# Top.net
KiCad netlist of a schematic drawn in Altium Designer
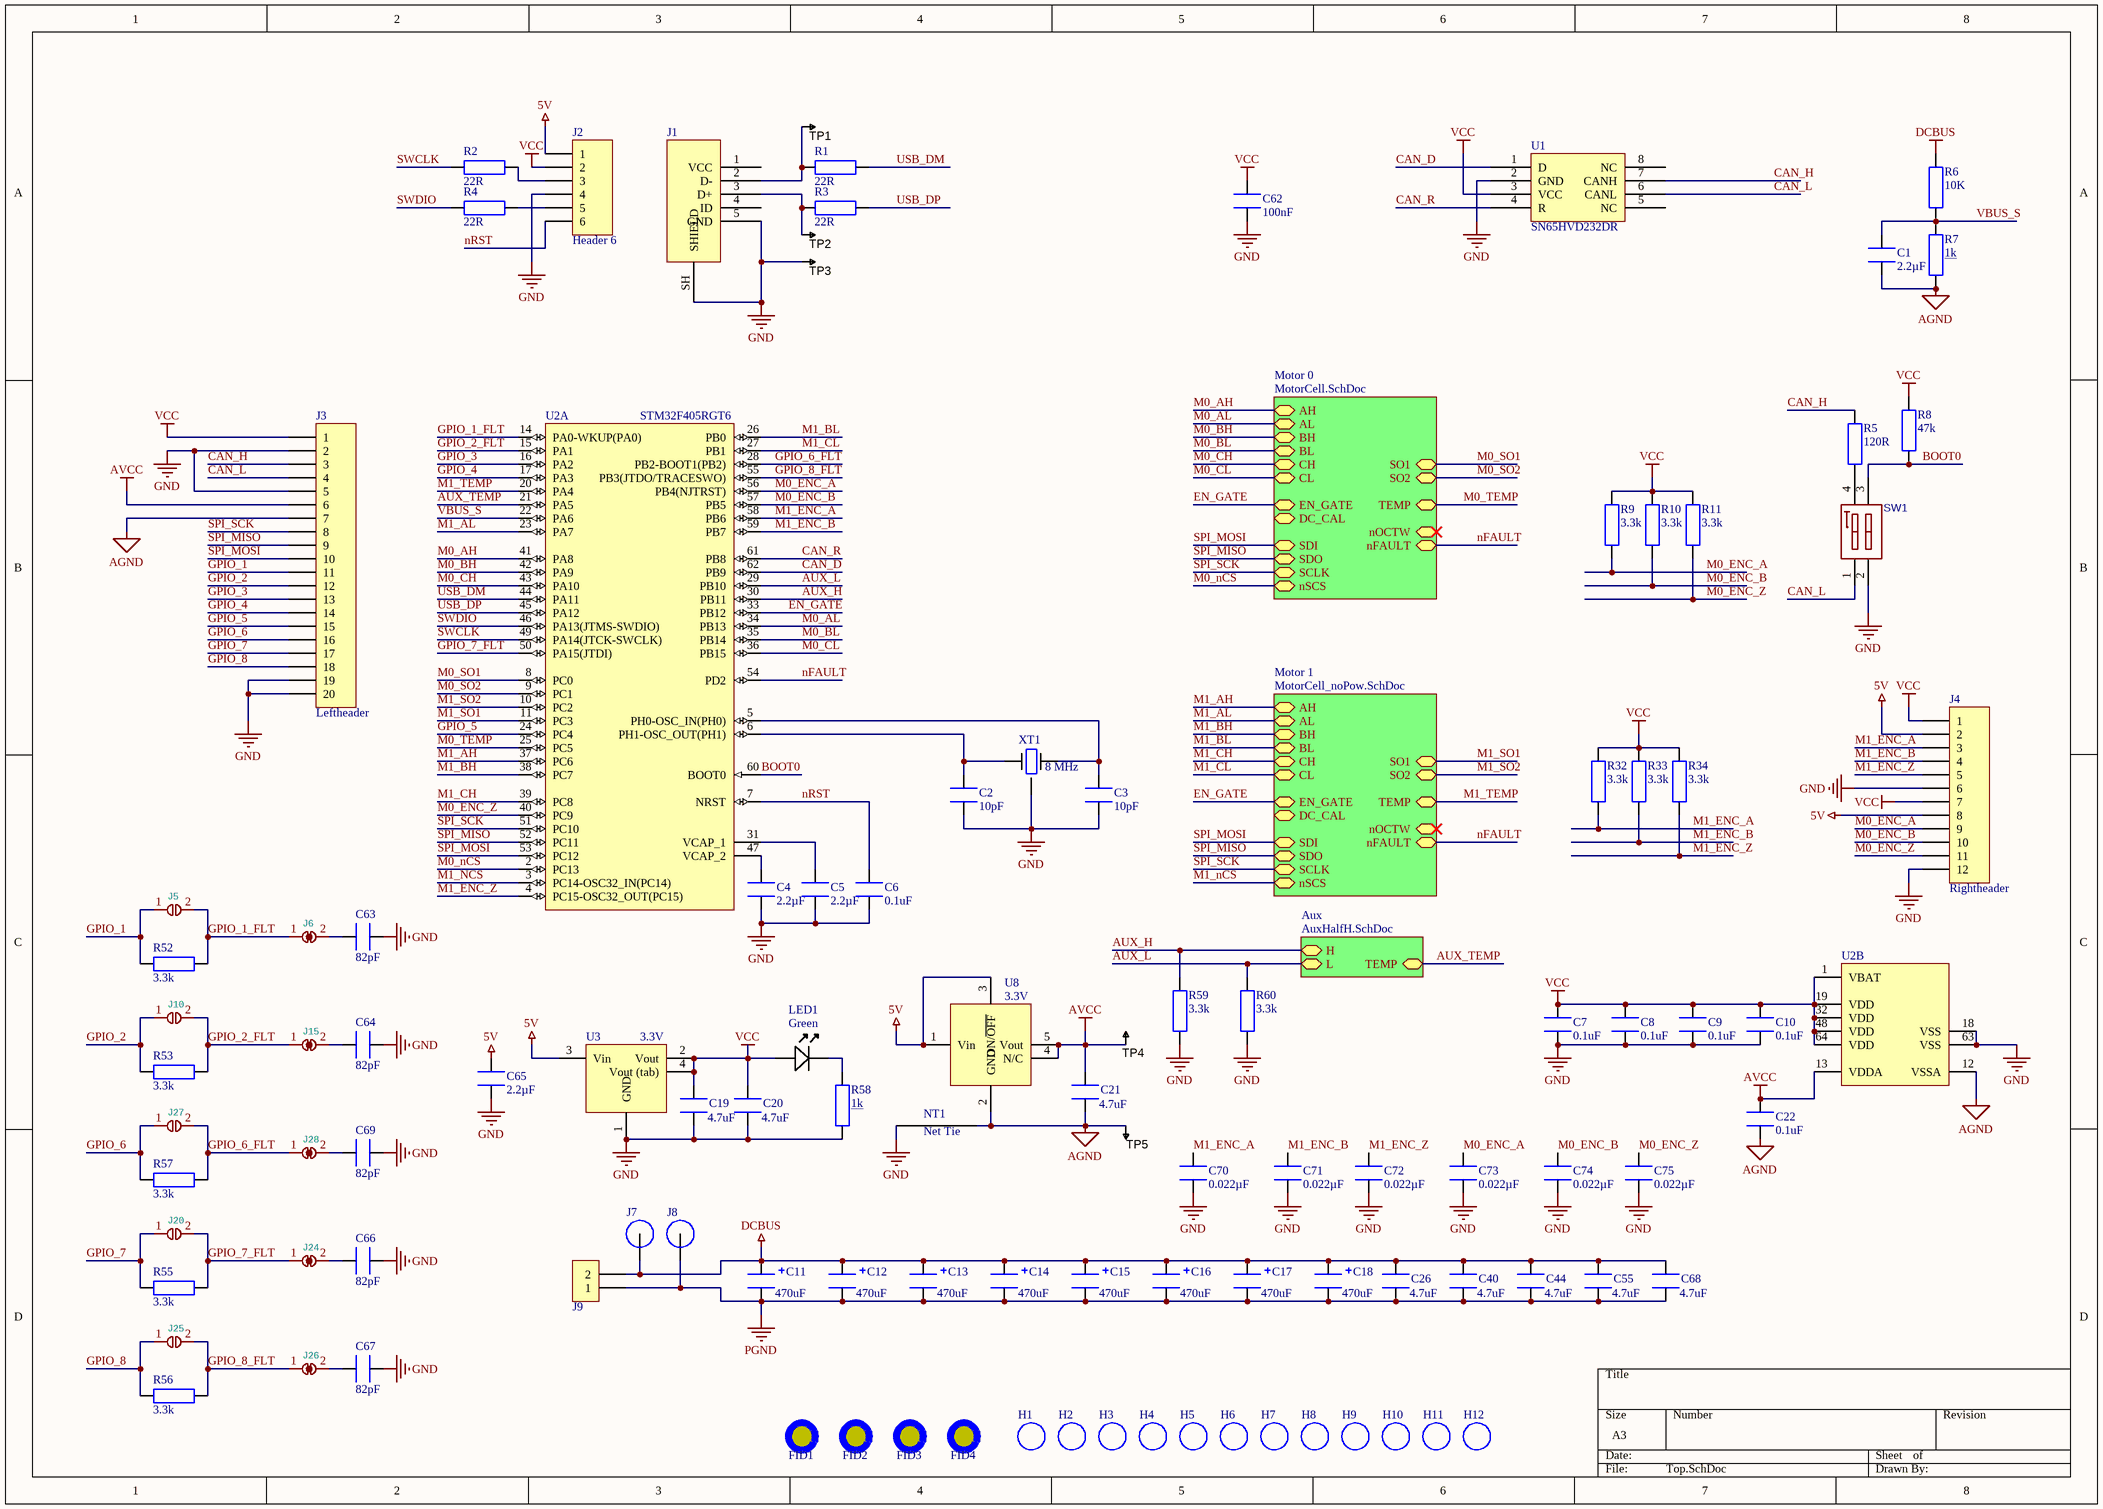
[diagram p0: Top.SchDoc]

(export (version "E")
  (design (tool "Eeschema 10.0.6"))
  (components
    (comp (ref "C1")
      (value "2.2µF")
      (footprint "CAPC1608X09L")
      (description "CAP CER 2.2UF 16V X5R 0603")
      (fields
        (field (name "MANUFACTURER") "Murata Electronics North America")
        (field (name "MANUFACTURER PART NUMBER") "GRM188R61C225KE15D")
      )
      (libsource (lib "CustomComponents") (part "GRM188R61C225KE15D"))
    )
    (comp (ref "C2")
      (value "10pF")
      (footprint "CAPC1608X09L")
      (description "CAP CER 10PF 50V NP0 0603")
      (fields
        (field (name "MANUFACTURER") "Murata Electronics North America")
        (field (name "MANUFACTURER PART NUMBER") "GRM1885C1H100JA01D")
      )
      (libsource (lib "CustomComponents") (part "GRM1885C1H100JA01D"))
    )
    (comp (ref "C3")
      (value "10pF")
      (footprint "CAPC1608X09L")
      (description "CAP CER 10PF 50V NP0 0603")
      (fields
        (field (name "MANUFACTURER") "Murata Electronics North America")
        (field (name "MANUFACTURER PART NUMBER") "GRM1885C1H100JA01D")
      )
      (libsource (lib "CustomComponents") (part "GRM1885C1H100JA01D"))
    )
    (comp (ref "C4")
      (value "2.2µF")
      (footprint "CAPC1608X09L")
      (description "CAP CER 2.2UF 16V X5R 0603")
      (fields
        (field (name "MANUFACTURER") "Murata Electronics North America")
        (field (name "MANUFACTURER PART NUMBER") "GRM188R61C225KE15D")
      )
      (libsource (lib "CustomComponents") (part "GRM188R61C225KE15D"))
    )
    (comp (ref "C5")
      (value "2.2µF")
      (footprint "CAPC1608X09L")
      (description "CAP CER 2.2UF 16V X5R 0603")
      (fields
        (field (name "MANUFACTURER") "Murata Electronics North America")
        (field (name "MANUFACTURER PART NUMBER") "GRM188R61C225KE15D")
      )
      (libsource (lib "CustomComponents") (part "GRM188R61C225KE15D"))
    )
    (comp (ref "C6")
      (value "0.1uF")
      (footprint "CAPC1608X09L")
      (description "CAP CER 0.1UF 50V X7R 0603")
      (fields
        (field (name "MANUFACTURER") "Murata Electronics North America")
        (field (name "MANUFACTURER PART NUMBER") "GRM188R71H104KA93D")
      )
      (libsource (lib "CustomComponents") (part "GRM188R71H104KA93D"))
    )
    (comp (ref "C7")
      (value "0.1uF")
      (footprint "CAPC1608X09L")
      (description "CAP CER 0.1UF 50V X7R 0603")
      (fields
        (field (name "MANUFACTURER") "Murata Electronics North America")
        (field (name "MANUFACTURER PART NUMBER") "GRM188R71H104KA93D")
      )
      (libsource (lib "CustomComponents") (part "GRM188R71H104KA93D"))
    )
    (comp (ref "C8")
      (value "0.1uF")
      (footprint "CAPC1608X09L")
      (description "CAP CER 0.1UF 50V X7R 0603")
      (fields
        (field (name "MANUFACTURER") "Murata Electronics North America")
        (field (name "MANUFACTURER PART NUMBER") "GRM188R71H104KA93D")
      )
      (libsource (lib "CustomComponents") (part "GRM188R71H104KA93D"))
    )
    (comp (ref "C9")
      (value "0.1uF")
      (footprint "CAPC1608X09L")
      (description "CAP CER 0.1UF 50V X7R 0603")
      (fields
        (field (name "MANUFACTURER") "Murata Electronics North America")
        (field (name "MANUFACTURER PART NUMBER") "GRM188R71H104KA93D")
      )
      (libsource (lib "CustomComponents") (part "GRM188R71H104KA93D"))
    )
    (comp (ref "C10")
      (value "0.1uF")
      (footprint "CAPC1608X09L")
      (description "CAP CER 0.1UF 50V X7R 0603")
      (fields
        (field (name "MANUFACTURER") "Murata Electronics North America")
        (field (name "MANUFACTURER PART NUMBER") "GRM188R71H104KA93D")
      )
      (libsource (lib "CustomComponents") (part "GRM188R71H104KA93D"))
    )
    (comp (ref "C11")
      (value "470uF")
      (footprint "CAP_ELEC_SIZE_G")
      (description "CAP, FP Series, 470 µF, 25 V, Radial Can - SMD, 10 mm")
      (fields
        (field (name "MANUFACTURER") "Panasonic Electronic Components")
        (field (name "TOLERANCE") "±20%")
      )
      (libsource (lib "CustomComponents") (part "EEEFP1E471AP"))
    )
    (comp (ref "C12")
      (value "470uF")
      (footprint "CAP_ELEC_SIZE_G")
      (description "CAP, FP Series, 470 µF, 25 V, Radial Can - SMD, 10 mm")
      (fields
        (field (name "MANUFACTURER") "Panasonic Electronic Components")
        (field (name "TOLERANCE") "±20%")
      )
      (libsource (lib "CustomComponents") (part "EEEFP1E471AP"))
    )
    (comp (ref "C13")
      (value "470uF")
      (footprint "CAP_ELEC_SIZE_G")
      (description "CAP, FP Series, 470 µF, 25 V, Radial Can - SMD, 10 mm")
      (fields
        (field (name "MANUFACTURER") "Panasonic Electronic Components")
        (field (name "TOLERANCE") "±20%")
      )
      (libsource (lib "CustomComponents") (part "EEEFP1E471AP"))
    )
    (comp (ref "C14")
      (value "470uF")
      (footprint "CAP_ELEC_SIZE_G")
      (description "CAP, FP Series, 470 µF, 25 V, Radial Can - SMD, 10 mm")
      (fields
        (field (name "MANUFACTURER") "Panasonic Electronic Components")
        (field (name "TOLERANCE") "±20%")
      )
      (libsource (lib "CustomComponents") (part "EEEFP1E471AP"))
    )
    (comp (ref "C15")
      (value "470uF")
      (footprint "CAP_ELEC_SIZE_G")
      (description "CAP, FP Series, 470 µF, 25 V, Radial Can - SMD, 10 mm")
      (fields
        (field (name "MANUFACTURER") "Panasonic Electronic Components")
        (field (name "TOLERANCE") "±20%")
      )
      (libsource (lib "CustomComponents") (part "EEEFP1E471AP"))
    )
    (comp (ref "C16")
      (value "470uF")
      (footprint "CAP_ELEC_SIZE_G")
      (description "CAP, FP Series, 470 µF, 25 V, Radial Can - SMD, 10 mm")
      (fields
        (field (name "MANUFACTURER") "Panasonic Electronic Components")
        (field (name "TOLERANCE") "±20%")
      )
      (libsource (lib "CustomComponents") (part "EEEFP1E471AP"))
    )
    (comp (ref "C17")
      (value "470uF")
      (footprint "CAP_ELEC_SIZE_G")
      (description "CAP, FP Series, 470 µF, 25 V, Radial Can - SMD, 10 mm")
      (fields
        (field (name "MANUFACTURER") "Panasonic Electronic Components")
        (field (name "TOLERANCE") "±20%")
      )
      (libsource (lib "CustomComponents") (part "EEEFP1E471AP"))
    )
    (comp (ref "C18")
      (value "470uF")
      (footprint "CAP_ELEC_SIZE_G")
      (description "CAP, FP Series, 470 µF, 25 V, Radial Can - SMD, 10 mm")
      (fields
        (field (name "MANUFACTURER") "Panasonic Electronic Components")
        (field (name "TOLERANCE") "±20%")
      )
      (libsource (lib "CustomComponents") (part "EEEFP1E471AP"))
    )
    (comp (ref "C19")
      (value "4.7uF")
      (footprint "CAPC2012X09N")
      (description "CAP CER 4.7UF 35V X5R 0805")
      (fields
        (field (name "MANUFACTURER") "Murata Electronics North America")
        (field (name "TOLERANCE") "±10%")
      )
      (libsource (lib "CustomComponents") (part "GRM219R6YA475KA73D"))
    )
    (comp (ref "C20")
      (value "4.7uF")
      (footprint "CAPC2012X09N")
      (description "CAP CER 4.7UF 35V X5R 0805")
      (fields
        (field (name "MANUFACTURER") "Murata Electronics North America")
        (field (name "TOLERANCE") "±10%")
      )
      (libsource (lib "CustomComponents") (part "GRM219R6YA475KA73D"))
    )
    (comp (ref "C21")
      (value "4.7uF")
      (footprint "CAPC2012X09N")
      (description "CAP CER 4.7UF 35V X5R 0805")
      (fields
        (field (name "MANUFACTURER") "Murata Electronics North America")
        (field (name "TOLERANCE") "±10%")
      )
      (libsource (lib "CustomComponents") (part "GRM219R6YA475KA73D"))
    )
    (comp (ref "C22")
      (value "0.1uF")
      (footprint "CAPC1608X09L")
      (description "CAP CER 0.1UF 50V X7R 0603")
      (fields
        (field (name "MANUFACTURER") "Murata Electronics North America")
        (field (name "MANUFACTURER PART NUMBER") "GRM188R71H104KA93D")
      )
      (libsource (lib "CustomComponents") (part "GRM188R71H104KA93D"))
    )
    (comp (ref "C26")
      (value "4.7uF")
      (footprint "CAPC2012X09N")
      (description "CAP CER 4.7UF 35V X5R 0805")
      (fields
        (field (name "MANUFACTURER") "Murata Electronics North America")
        (field (name "TOLERANCE") "±10%")
      )
      (libsource (lib "CustomComponents") (part "GRM219R6YA475KA73D"))
    )
    (comp (ref "C40")
      (value "4.7uF")
      (footprint "CAPC2012X09N")
      (description "CAP CER 4.7UF 35V X5R 0805")
      (fields
        (field (name "MANUFACTURER") "Murata Electronics North America")
        (field (name "TOLERANCE") "±10%")
      )
      (libsource (lib "CustomComponents") (part "GRM219R6YA475KA73D"))
    )
    (comp (ref "C44")
      (value "4.7uF")
      (footprint "CAPC2012X09N")
      (description "CAP CER 4.7UF 35V X5R 0805")
      (fields
        (field (name "MANUFACTURER") "Murata Electronics North America")
        (field (name "TOLERANCE") "±10%")
      )
      (libsource (lib "CustomComponents") (part "GRM219R6YA475KA73D"))
    )
    (comp (ref "C55")
      (value "4.7uF")
      (footprint "CAPC2012X09N")
      (description "CAP CER 4.7UF 35V X5R 0805")
      (fields
        (field (name "MANUFACTURER") "Murata Electronics North America")
        (field (name "TOLERANCE") "±10%")
      )
      (libsource (lib "CustomComponents") (part "GRM219R6YA475KA73D"))
    )
    (comp (ref "C62")
      (value "100nF")
      (footprint "1608[0603]")
      (description "CAP, MLCC, X7R, 100NF, 16V, 0603")
      (fields (field (name "Comment") "MC0603B104K160CT"))
      (libsource (lib "CustomComponents") (part "MC0603B104K160CT"))
    )
    (comp (ref "C63")
      (value "82pF")
      (footprint "CAPC1608X09L")
      (description "CAP CER 82PF 100V NP0 0603")
      (fields
        (field (name "MANUFACTURER") "Murata Electronics North America")
        (field (name "MANUFACTURER PART NUMBER") "GRM1885C2A820JA01D")
      )
      (libsource (lib "CustomComponents") (part "GRM1885C2A820JA01D"))
    )
    (comp (ref "C64")
      (value "82pF")
      (footprint "CAPC1608X09L")
      (description "CAP CER 82PF 100V NP0 0603")
      (fields
        (field (name "MANUFACTURER") "Murata Electronics North America")
        (field (name "MANUFACTURER PART NUMBER") "GRM1885C2A820JA01D")
      )
      (libsource (lib "CustomComponents") (part "GRM1885C2A820JA01D"))
    )
    (comp (ref "C65")
      (value "2.2µF")
      (footprint "CAPC1608X09L")
      (description "CAP CER 2.2UF 16V X5R 0603")
      (fields
        (field (name "MANUFACTURER") "Murata Electronics North America")
        (field (name "MANUFACTURER PART NUMBER") "GRM188R61C225KE15D")
      )
      (libsource (lib "CustomComponents") (part "GRM188R61C225KE15D"))
    )
    (comp (ref "C66")
      (value "82pF")
      (footprint "CAPC1608X09L")
      (description "CAP CER 82PF 100V NP0 0603")
      (fields
        (field (name "MANUFACTURER") "Murata Electronics North America")
        (field (name "MANUFACTURER PART NUMBER") "GRM1885C2A820JA01D")
      )
      (libsource (lib "CustomComponents") (part "GRM1885C2A820JA01D"))
    )
    (comp (ref "C67")
      (value "82pF")
      (footprint "CAPC1608X09L")
      (description "CAP CER 82PF 100V NP0 0603")
      (fields
        (field (name "MANUFACTURER") "Murata Electronics North America")
        (field (name "MANUFACTURER PART NUMBER") "GRM1885C2A820JA01D")
      )
      (libsource (lib "CustomComponents") (part "GRM1885C2A820JA01D"))
    )
    (comp (ref "C68")
      (value "4.7uF")
      (footprint "CAPC2012X09N")
      (description "CAP CER 4.7UF 35V X5R 0805")
      (fields
        (field (name "MANUFACTURER") "Murata Electronics North America")
        (field (name "TOLERANCE") "±10%")
      )
      (libsource (lib "CustomComponents") (part "GRM219R6YA475KA73D"))
    )
    (comp (ref "C69")
      (value "82pF")
      (footprint "CAPC1608X09L")
      (description "CAP CER 82PF 100V NP0 0603")
      (fields
        (field (name "MANUFACTURER") "Murata Electronics North America")
        (field (name "MANUFACTURER PART NUMBER") "GRM1885C2A820JA01D")
      )
      (libsource (lib "CustomComponents") (part "GRM1885C2A820JA01D"))
    )
    (comp (ref "C70")
      (value "0.022µF")
      (footprint "CAPC1608X09L")
      (description "CAP CER 0.022UF 50V X7R 0603")
      (fields
        (field (name "MANUFACTURER") "Murata Electronics North America")
        (field (name "MANUFACTURER PART NUMBER") "GRM188R71H223KA01D")
      )
      (libsource (lib "CustomComponents") (part "GRM188R71H223KA01D"))
    )
    (comp (ref "C71")
      (value "0.022µF")
      (footprint "CAPC1608X09L")
      (description "CAP CER 0.022UF 50V X7R 0603")
      (fields
        (field (name "MANUFACTURER") "Murata Electronics North America")
        (field (name "MANUFACTURER PART NUMBER") "GRM188R71H223KA01D")
      )
      (libsource (lib "CustomComponents") (part "GRM188R71H223KA01D"))
    )
    (comp (ref "C72")
      (value "0.022µF")
      (footprint "CAPC1608X09L")
      (description "CAP CER 0.022UF 50V X7R 0603")
      (fields
        (field (name "MANUFACTURER") "Murata Electronics North America")
        (field (name "MANUFACTURER PART NUMBER") "GRM188R71H223KA01D")
      )
      (libsource (lib "CustomComponents") (part "GRM188R71H223KA01D"))
    )
    (comp (ref "C73")
      (value "0.022µF")
      (footprint "CAPC1608X09L")
      (description "CAP CER 0.022UF 50V X7R 0603")
      (fields
        (field (name "MANUFACTURER") "Murata Electronics North America")
        (field (name "MANUFACTURER PART NUMBER") "GRM188R71H223KA01D")
      )
      (libsource (lib "CustomComponents") (part "GRM188R71H223KA01D"))
    )
    (comp (ref "C74")
      (value "0.022µF")
      (footprint "CAPC1608X09L")
      (description "CAP CER 0.022UF 50V X7R 0603")
      (fields
        (field (name "MANUFACTURER") "Murata Electronics North America")
        (field (name "MANUFACTURER PART NUMBER") "GRM188R71H223KA01D")
      )
      (libsource (lib "CustomComponents") (part "GRM188R71H223KA01D"))
    )
    (comp (ref "C75")
      (value "0.022µF")
      (footprint "CAPC1608X09L")
      (description "CAP CER 0.022UF 50V X7R 0603")
      (fields
        (field (name "MANUFACTURER") "Murata Electronics North America")
        (field (name "MANUFACTURER PART NUMBER") "GRM188R71H223KA01D")
      )
      (libsource (lib "CustomComponents") (part "GRM188R71H223KA01D"))
    )
    (comp (ref "FID1")
      (value "FIDUCIAL")
      (footprint "FIDUCIAL")
      (description "1mm Fiducial with 2mm soldermask, 3mm keepout")
      (libsource (lib "CustomComponents") (part "FIDUCIAL"))
    )
    (comp (ref "FID2")
      (value "FIDUCIAL")
      (footprint "FIDUCIAL")
      (description "1mm Fiducial with 2mm soldermask, 3mm keepout")
      (libsource (lib "CustomComponents") (part "FIDUCIAL"))
    )
    (comp (ref "FID3")
      (value "FIDUCIAL")
      (footprint "FIDUCIAL")
      (description "1mm Fiducial with 2mm soldermask, 3mm keepout")
      (libsource (lib "CustomComponents") (part "FIDUCIAL"))
    )
    (comp (ref "FID4")
      (value "FIDUCIAL")
      (footprint "FIDUCIAL")
      (description "1mm Fiducial with 2mm soldermask, 3mm keepout")
      (libsource (lib "CustomComponents") (part "FIDUCIAL"))
    )
    (comp (ref "H1")
      (value "~")
      (footprint "M3 Hole")
      (description "M3 Hole with no copper")
      (libsource (lib "CustomComponents") (part "M3 Hole"))
    )
    (comp (ref "H2")
      (value "~")
      (footprint "M3 Hole")
      (description "M3 Hole with no copper")
      (libsource (lib "CustomComponents") (part "M3 Hole"))
    )
    (comp (ref "H3")
      (value "~")
      (footprint "M3 Hole")
      (description "M3 Hole with no copper")
      (libsource (lib "CustomComponents") (part "M3 Hole"))
    )
    (comp (ref "H4")
      (value "~")
      (footprint "M3 Hole")
      (description "M3 Hole with no copper")
      (libsource (lib "CustomComponents") (part "M3 Hole"))
    )
    (comp (ref "H5")
      (value "~")
      (footprint "M3 Hole")
      (description "M3 Hole with no copper")
      (libsource (lib "CustomComponents") (part "M3 Hole"))
    )
    (comp (ref "H6")
      (value "~")
      (footprint "M3 Hole")
      (description "M3 Hole with no copper")
      (libsource (lib "CustomComponents") (part "M3 Hole"))
    )
    (comp (ref "H7")
      (value "~")
      (footprint "M3 Hole")
      (description "M3 Hole with no copper")
      (libsource (lib "CustomComponents") (part "M3 Hole"))
    )
    (comp (ref "H8")
      (value "~")
      (footprint "M3 Hole")
      (description "M3 Hole with no copper")
      (libsource (lib "CustomComponents") (part "M3 Hole"))
    )
    (comp (ref "H9")
      (value "~")
      (footprint "M3 Hole")
      (description "M3 Hole with no copper")
      (libsource (lib "CustomComponents") (part "M3 Hole"))
    )
    (comp (ref "H10")
      (value "~")
      (footprint "M3 Hole")
      (description "M3 Hole with no copper")
      (libsource (lib "CustomComponents") (part "M3 Hole"))
    )
    (comp (ref "H11")
      (value "~")
      (footprint "M3 Hole")
      (description "M3 Hole with no copper")
      (libsource (lib "CustomComponents") (part "M3 Hole"))
    )
    (comp (ref "H12")
      (value "~")
      (footprint "M3 Hole")
      (description "M3 Hole with no copper")
      (libsource (lib "CustomComponents") (part "M3 Hole"))
    )
    (comp (ref "J1")
      (value "~")
      (footprint "USB_0103594-0001LF")
      (description "MICRO USB B, RECEPTACLE, SMT, RA, 5WAY")
      (libsource (lib "CustomComponents") (part "10103594-0001LF"))
    )
    (comp (ref "J2")
      (value "Header 6")
      (footprint "HDR1X6")
      (description "Header, 6-Pin")
      (fields (field (name "PUBLISHER") "Altium Limited"))
      (libsource (lib "Miscellaneous Connectors") (part "Header 6"))
    )
    (comp (ref "J3")
      (value "Leftheader")
      (footprint "HDR1X20")
      (description "Header, 20-Pin")
      (fields (field (name "PUBLISHER") "Altium Limited"))
      (libsource (lib "Miscellaneous Connectors") (part "Header 20"))
    )
    (comp (ref "J4")
      (value "Rightheader")
      (footprint "HDR1X12")
      (description "Header, 12-Pin")
      (fields (field (name "PUBLISHER") "Altium Limited"))
      (libsource (lib "Miscellaneous Connectors") (part "Header 12"))
    )
    (comp (ref "J5")
      (value "SolderJumper_2_Open")
      (footprint "SOLDERJUMPER-2_P1.3MM_OPEN_PAD1.0X1.5MM")
      (libsource (lib "CustomComponents") (part "SolderJumper_2_Open"))
    )
    (comp (ref "J6")
      (value "SolderJumper_2_Bridged")
      (footprint "SOLDERJUMPER-2_P1.3MM_BRIDGED_PAD1.0X1.5MM")
      (libsource (lib "CustomComponents") (part "SolderJumper_2_Bridged"))
    )
    (comp (ref "J7")
      (value "~")
      (footprint "M3 Spade Hole")
      (description "M3 Spade Terminal")
      (libsource (lib "CustomComponents") (part "M3 Spade Terminal"))
    )
    (comp (ref "J8")
      (value "~")
      (footprint "M3 Spade Hole")
      (description "M3 Spade Terminal")
      (libsource (lib "CustomComponents") (part "M3 Spade Terminal"))
    )
    (comp (ref "J9")
      (value "1868076")
      (footprint "1868076")
      (description "CONN TERM BLOCK 2POS 7.62MM")
      (fields (field (name "MANUFACTURER") "Phoenix Contact") (field (name "VOLTAGE") "300V"))
      (libsource (lib "CustomComponents") (part "1868076"))
    )
    (comp (ref "J10")
      (value "SolderJumper_2_Open")
      (footprint "SOLDERJUMPER-2_P1.3MM_OPEN_PAD1.0X1.5MM")
      (libsource (lib "CustomComponents") (part "SolderJumper_2_Open"))
    )
    (comp (ref "J15")
      (value "SolderJumper_2_Bridged")
      (footprint "SOLDERJUMPER-2_P1.3MM_BRIDGED_PAD1.0X1.5MM")
      (libsource (lib "CustomComponents") (part "SolderJumper_2_Bridged"))
    )
    (comp (ref "J20")
      (value "SolderJumper_2_Open")
      (footprint "SOLDERJUMPER-2_P1.3MM_OPEN_PAD1.0X1.5MM")
      (libsource (lib "CustomComponents") (part "SolderJumper_2_Open"))
    )
    (comp (ref "J24")
      (value "SolderJumper_2_Bridged")
      (footprint "SOLDERJUMPER-2_P1.3MM_BRIDGED_PAD1.0X1.5MM")
      (libsource (lib "CustomComponents") (part "SolderJumper_2_Bridged"))
    )
    (comp (ref "J25")
      (value "SolderJumper_2_Open")
      (footprint "SOLDERJUMPER-2_P1.3MM_OPEN_PAD1.0X1.5MM")
      (libsource (lib "CustomComponents") (part "SolderJumper_2_Open"))
    )
    (comp (ref "J26")
      (value "SolderJumper_2_Bridged")
      (footprint "SOLDERJUMPER-2_P1.3MM_BRIDGED_PAD1.0X1.5MM")
      (libsource (lib "CustomComponents") (part "SolderJumper_2_Bridged"))
    )
    (comp (ref "J27")
      (value "SolderJumper_2_Open")
      (footprint "SOLDERJUMPER-2_P1.3MM_OPEN_PAD1.0X1.5MM")
      (libsource (lib "CustomComponents") (part "SolderJumper_2_Open"))
    )
    (comp (ref "J28")
      (value "SolderJumper_2_Bridged")
      (footprint "SOLDERJUMPER-2_P1.3MM_BRIDGED_PAD1.0X1.5MM")
      (libsource (lib "CustomComponents") (part "SolderJumper_2_Bridged"))
    )
    (comp (ref "LED1")
      (value "Green")
      (footprint "LED-0603-GREEN")
      (description "LED GREEN CLEAR 0603 SMD")
      (fields
        (field (name "MANUFACTURER") "Lite-On Inc.")
        (field (name "MANUFACTURER PART NUMBER") "LTST-C190KGKT")
      )
      (libsource (lib "CustomComponents") (part "LTST-C190KGKT"))
    )
    (comp (ref "NT1")
      (value "~")
      (footprint "NetTie_2mm")
      (libsource (lib "CustomComponents") (part "NetTie_2mm"))
    )
    (comp (ref "R1")
      (value "22R")
      (footprint "RESC1608X55N")
      (description "RES SMD 22 OHM 1% 1/10W 0603")
      (fields
        (field (name "MANUFACTURER") "Yageo")
        (field (name "MANUFACTURER PART NUMBER") "RC0603FR-0722RL")
      )
      (libsource (lib "CustomComponents") (part "RC0603FR-0722RL"))
    )
    (comp (ref "R2")
      (value "22R")
      (footprint "RESC1608X55N")
      (description "RES SMD 22 OHM 1% 1/10W 0603")
      (fields
        (field (name "MANUFACTURER") "Yageo")
        (field (name "MANUFACTURER PART NUMBER") "RC0603FR-0722RL")
      )
      (libsource (lib "CustomComponents") (part "RC0603FR-0722RL"))
    )
    (comp (ref "R3")
      (value "22R")
      (footprint "RESC1608X55N")
      (description "RES SMD 22 OHM 1% 1/10W 0603")
      (fields
        (field (name "MANUFACTURER") "Yageo")
        (field (name "MANUFACTURER PART NUMBER") "RC0603FR-0722RL")
      )
      (libsource (lib "CustomComponents") (part "RC0603FR-0722RL"))
    )
    (comp (ref "R4")
      (value "22R")
      (footprint "RESC1608X55N")
      (description "RES SMD 22 OHM 1% 1/10W 0603")
      (fields
        (field (name "MANUFACTURER") "Yageo")
        (field (name "MANUFACTURER PART NUMBER") "RC0603FR-0722RL")
      )
      (libsource (lib "CustomComponents") (part "RC0603FR-0722RL"))
    )
    (comp (ref "R5")
      (value "120R")
      (footprint "RESC1608X55N")
      (description "RES SMD 120 OHM 1% 1/10W 0603")
      (fields
        (field (name "MANUFACTURER") "Yageo")
        (field (name "MANUFACTURER PART NUMBER") "RC0603FR-07120RL")
      )
      (libsource (lib "CustomComponents") (part "RC0603FR-07120RL"))
    )
    (comp (ref "R6")
      (value "10K")
      (footprint "RESC1608X55N")
      (description "RES SMD 10K OHM 1% 1/10W 0603")
      (fields
        (field (name "MANUFACTURER") "Yageo")
        (field (name "MANUFACTURER PART NUMBER") "RC0603FR-0710KL")
      )
      (libsource (lib "CustomComponents") (part "RC0603FR-0710KL"))
    )
    (comp (ref "R7")
      (value "1k")
      (footprint "RESC1608X55N")
      (description "RES SMD 1K OHM 1% 1/10W 0603")
      (fields (field (name "MANUFACTURER") "Yageo") (field (name "TOLERANCE") "±1%"))
      (libsource (lib "CustomComponents") (part "RC0603FR-071KL"))
    )
    (comp (ref "R8")
      (value "47k")
      (footprint "RESC1608X55N")
      (description "RES SMD 3.3K OHM 1% 1/10W 0603")
      (fields (field (name "MANUFACTURER") "Yageo") (field (name "TOLERANCE") "±1%"))
      (libsource (lib "CustomComponents") (part "RC0603FR-073K3L"))
    )
    (comp (ref "R9")
      (value "3.3k")
      (footprint "RESC1608X55N")
      (description "RES SMD 3.3K OHM 1% 1/10W 0603")
      (fields (field (name "MANUFACTURER") "Yageo") (field (name "TOLERANCE") "±1%"))
      (libsource (lib "CustomComponents") (part "RC0603FR-073K3L"))
    )
    (comp (ref "R10")
      (value "3.3k")
      (footprint "RESC1608X55N")
      (description "RES SMD 3.3K OHM 1% 1/10W 0603")
      (fields (field (name "MANUFACTURER") "Yageo") (field (name "TOLERANCE") "±1%"))
      (libsource (lib "CustomComponents") (part "RC0603FR-073K3L"))
    )
    (comp (ref "R11")
      (value "3.3k")
      (footprint "RESC1608X55N")
      (description "RES SMD 3.3K OHM 1% 1/10W 0603")
      (fields (field (name "MANUFACTURER") "Yageo") (field (name "TOLERANCE") "±1%"))
      (libsource (lib "CustomComponents") (part "RC0603FR-073K3L"))
    )
    (comp (ref "R32")
      (value "3.3k")
      (footprint "RESC1608X55N")
      (description "RES SMD 3.3K OHM 1% 1/10W 0603")
      (fields (field (name "MANUFACTURER") "Yageo") (field (name "TOLERANCE") "±1%"))
      (libsource (lib "CustomComponents") (part "RC0603FR-073K3L"))
    )
    (comp (ref "R33")
      (value "3.3k")
      (footprint "RESC1608X55N")
      (description "RES SMD 3.3K OHM 1% 1/10W 0603")
      (fields (field (name "MANUFACTURER") "Yageo") (field (name "TOLERANCE") "±1%"))
      (libsource (lib "CustomComponents") (part "RC0603FR-073K3L"))
    )
    (comp (ref "R34")
      (value "3.3k")
      (footprint "RESC1608X55N")
      (description "RES SMD 3.3K OHM 1% 1/10W 0603")
      (fields (field (name "MANUFACTURER") "Yageo") (field (name "TOLERANCE") "±1%"))
      (libsource (lib "CustomComponents") (part "RC0603FR-073K3L"))
    )
    (comp (ref "R52")
      (value "3.3k")
      (footprint "RESC1608X55N")
      (description "RES SMD 3.3K OHM 1% 1/10W 0603")
      (fields (field (name "MANUFACTURER") "Yageo") (field (name "TOLERANCE") "±1%"))
      (libsource (lib "CustomComponents") (part "RC0603FR-073K3L"))
    )
    (comp (ref "R53")
      (value "3.3k")
      (footprint "RESC1608X55N")
      (description "RES SMD 3.3K OHM 1% 1/10W 0603")
      (fields (field (name "MANUFACTURER") "Yageo") (field (name "TOLERANCE") "±1%"))
      (libsource (lib "CustomComponents") (part "RC0603FR-073K3L"))
    )
    (comp (ref "R55")
      (value "3.3k")
      (footprint "RESC1608X55N")
      (description "RES SMD 3.3K OHM 1% 1/10W 0603")
      (fields (field (name "MANUFACTURER") "Yageo") (field (name "TOLERANCE") "±1%"))
      (libsource (lib "CustomComponents") (part "RC0603FR-073K3L"))
    )
    (comp (ref "R56")
      (value "3.3k")
      (footprint "RESC1608X55N")
      (description "RES SMD 3.3K OHM 1% 1/10W 0603")
      (fields (field (name "MANUFACTURER") "Yageo") (field (name "TOLERANCE") "±1%"))
      (libsource (lib "CustomComponents") (part "RC0603FR-073K3L"))
    )
    (comp (ref "R57")
      (value "3.3k")
      (footprint "RESC1608X55N")
      (description "RES SMD 3.3K OHM 1% 1/10W 0603")
      (fields (field (name "MANUFACTURER") "Yageo") (field (name "TOLERANCE") "±1%"))
      (libsource (lib "CustomComponents") (part "RC0603FR-073K3L"))
    )
    (comp (ref "R58")
      (value "1k")
      (footprint "RESC1608X55N")
      (description "RES SMD 1K OHM 1% 1/10W 0603")
      (fields (field (name "MANUFACTURER") "Yageo") (field (name "TOLERANCE") "±1%"))
      (libsource (lib "CustomComponents") (part "RC0603FR-071KL"))
    )
    (comp (ref "R59")
      (value "3.3k")
      (footprint "RESC1608X55N")
      (description "RES SMD 3.3K OHM 1% 1/10W 0603")
      (fields (field (name "MANUFACTURER") "Yageo") (field (name "TOLERANCE") "±1%"))
      (libsource (lib "CustomComponents") (part "RC0603FR-073K3L"))
    )
    (comp (ref "R60")
      (value "3.3k")
      (footprint "RESC1608X55N")
      (description "RES SMD 3.3K OHM 1% 1/10W 0603")
      (fields (field (name "MANUFACTURER") "Yageo") (field (name "TOLERANCE") "±1%"))
      (libsource (lib "CustomComponents") (part "RC0603FR-073K3L"))
    )
    (comp (ref "SW1")
      (value "DSHP02TSGET")
      (footprint "SW-SMD_4P_DSHP02TSGET")
      (fields (field (name "BOM_SUPPLIER PART") "C40735"))
      (libsource (lib "CustomComponents") (part "DSHP02TSGET"))
    )
    (comp (ref "TP1")
      (value "TESTPOINT")
      (footprint "TP-R60")
      (description "SMD test pin")
      (libsource (lib "PBL - Test Points") (part "TESTPOINT"))
    )
    (comp (ref "TP2")
      (value "TESTPOINT")
      (footprint "TP-R60")
      (description "SMD test pin")
      (libsource (lib "PBL - Test Points") (part "TESTPOINT"))
    )
    (comp (ref "TP3")
      (value "TESTPOINT")
      (footprint "TP-R60")
      (description "SMD test pin")
      (libsource (lib "PBL - Test Points") (part "TESTPOINT"))
    )
    (comp (ref "TP4")
      (value "TESTPOINT")
      (footprint "TP-R30")
      (description "SMD test pin")
      (libsource (lib "PBL - Test Points") (part "TESTPOINT"))
    )
    (comp (ref "TP5")
      (value "TESTPOINT")
      (footprint "TP-R30")
      (description "SMD test pin")
      (libsource (lib "PBL - Test Points") (part "TESTPOINT"))
    )
    (comp (ref "U1")
      (value "SN65HVD232D")
      (footprint "SOIC127P600X175-8N")
      (fields
        (field (name "MANUFACTURER") "Texas Instruments")
        (field (name "MANUFACTURER PART NUMBER") "SN65HVD232DR")
      )
      (libsource (lib "CustomComponents") (part "SN65HVD232D"))
    )
    (comp (ref "U2")
      (value "~")
      (footprint "STM-LQFP64_N")
      (fields (field (name "MANUFACTURER") "STMicroelectronics") (field (name "PARTNUMBER") "STM32F405RGT6"))
      (libsource (lib "STMicroelectronics STM32 F4") (part "STM32F405RGT6"))
    )
    (comp (ref "U3")
      (value "3.3V")
      (footprint "SOT223")
      (description "IC REG LDO 3.3V 1A SOT223")
      (fields (field (name "MANUFACTURER") "Diodes Incorporated"))
      (libsource (lib "CustomComponents") (part "AZ1117EH-3.3TRG1"))
    )
    (comp (ref "U8")
      (value "3.3V")
      (footprint "SOT23-5")
      (description "IC REG LDO 3.3V 0.25A SOT23-5")
      (fields (field (name "MANUFACTURER") "Texas Instruments"))
      (libsource (lib "CustomComponents") (part "LP5907MFX-3.3/NOPB"))
    )
    (comp (ref "XT1")
      (value "8 MHz")
      (footprint "DFN220P320X110-4N")
      (description "Crystal 8MHz ±10ppm 10pF 200 Ohm -10°C ~ 60°C Surface Mount 4-SMD, No Lead (DFN, LCC)")
      (fields
        (field (name "MANUFACTURER") "Abracon LLC")
        (field (name "MANUFACTURER PART NUMBER") "ABM3B-8.000MHZ-10-1-U-T")
      )
      (libsource (lib "CustomComponents") (part "ABM3B-8.000MHZ-10-1-U-T"))
    )
  )
  (nets
    (net (code "1") (name "/AUX_H") (class "Default")
      (node (ref "R59") (pin "1") (pinfunction "0_1") (pintype "passive"))
      (node (ref "U2") (pin "30") (pinfunction "PB11_30") (pintype "bidirectional"))
    )
    (net (code "2") (name "/AUX_L") (class "Default")
      (node (ref "R60") (pin "1") (pinfunction "0_1") (pintype "passive"))
      (node (ref "U2") (pin "29") (pinfunction "PB10_29") (pintype "bidirectional"))
    )
    (net (code "3") (name "/AUX_TEMP") (class "Default")
      (node (ref "U2") (pin "21") (pinfunction "PA5_21") (pintype "bidirectional"))
    )
    (net (code "4") (name "/BOOT0") (class "Default")
      (node (ref "R8") (pin "2") (pinfunction "0_2") (pintype "passive"))
      (node (ref "SW1") (pin "3") (pinfunction "B2_3") (pintype "passive"))
      (node (ref "U2") (pin "60") (pinfunction "BOOT0_60") (pintype "input"))
    )
    (net (code "5") (name "/CAN_D") (class "Default")
      (node (ref "U1") (pin "1") (pinfunction "D_1") (pintype "passive"))
      (node (ref "U2") (pin "62") (pinfunction "PB9_62") (pintype "bidirectional"))
    )
    (net (code "6") (name "/CAN_H") (class "Default")
      (node (ref "J3") (pin "3") (pinfunction "3_3") (pintype "passive"))
      (node (ref "R5") (pin "2") (pinfunction "0_2") (pintype "passive"))
      (node (ref "U1") (pin "7") (pinfunction "CANH_7") (pintype "passive"))
    )
    (net (code "7") (name "/CAN_L") (class "Default")
      (node (ref "J3") (pin "4") (pinfunction "4_4") (pintype "passive"))
      (node (ref "SW1") (pin "1") (pinfunction "A1_1") (pintype "passive"))
      (node (ref "U1") (pin "6") (pinfunction "CANL_6") (pintype "passive"))
    )
    (net (code "8") (name "/CAN_R") (class "Default")
      (node (ref "U1") (pin "4") (pinfunction "R_4") (pintype "passive"))
      (node (ref "U2") (pin "61") (pinfunction "PB8_61") (pintype "bidirectional"))
    )
    (net (code "11") (name "/EN_GATE") (class "Default")
      (node (ref "U2") (pin "33") (pinfunction "PB12_33") (pintype "bidirectional"))
    )
    (net (code "12") (name "/GPIO_1") (class "Default")
      (node (ref "J3") (pin "11") (pinfunction "11_11") (pintype "passive"))
      (node (ref "J5") (pin "1") (pinfunction "A_1") (pintype "passive"))
      (node (ref "R52") (pin "1") (pinfunction "0_1") (pintype "passive"))
    )
    (net (code "13") (name "/GPIO_1_FLT") (class "Default")
      (node (ref "J5") (pin "2") (pinfunction "B_2") (pintype "passive"))
      (node (ref "J6") (pin "1") (pinfunction "A_1") (pintype "passive"))
      (node (ref "R52") (pin "2") (pinfunction "0_2") (pintype "passive"))
      (node (ref "U2") (pin "14") (pinfunction "PA0-WKUP(PA0)_14") (pintype "bidirectional"))
    )
    (net (code "14") (name "/GPIO_2") (class "Default")
      (node (ref "J10") (pin "1") (pinfunction "A_1") (pintype "passive"))
      (node (ref "J3") (pin "12") (pinfunction "12_12") (pintype "passive"))
      (node (ref "R53") (pin "1") (pinfunction "0_1") (pintype "passive"))
    )
    (net (code "15") (name "/GPIO_2_FLT") (class "Default")
      (node (ref "J10") (pin "2") (pinfunction "B_2") (pintype "passive"))
      (node (ref "J15") (pin "1") (pinfunction "A_1") (pintype "passive"))
      (node (ref "R53") (pin "2") (pinfunction "0_2") (pintype "passive"))
      (node (ref "U2") (pin "15") (pinfunction "PA1_15") (pintype "bidirectional"))
    )
    (net (code "16") (name "/GPIO_3") (class "Default")
      (node (ref "J3") (pin "13") (pinfunction "13_13") (pintype "passive"))
      (node (ref "U2") (pin "16") (pinfunction "PA2_16") (pintype "bidirectional"))
    )
    (net (code "17") (name "/GPIO_4") (class "Default")
      (node (ref "J3") (pin "14") (pinfunction "14_14") (pintype "passive"))
      (node (ref "U2") (pin "17") (pinfunction "PA3_17") (pintype "bidirectional"))
    )
    (net (code "18") (name "/GPIO_5") (class "Default")
      (node (ref "J3") (pin "15") (pinfunction "15_15") (pintype "passive"))
      (node (ref "U2") (pin "24") (pinfunction "PC4_24") (pintype "bidirectional"))
    )
    (net (code "19") (name "/GPIO_6") (class "Default")
      (node (ref "J27") (pin "1") (pinfunction "A_1") (pintype "passive"))
      (node (ref "J3") (pin "16") (pinfunction "16_16") (pintype "passive"))
      (node (ref "R57") (pin "1") (pinfunction "0_1") (pintype "passive"))
    )
    (net (code "20") (name "/GPIO_6_FLT") (class "Default")
      (node (ref "J27") (pin "2") (pinfunction "B_2") (pintype "passive"))
      (node (ref "J28") (pin "1") (pinfunction "A_1") (pintype "passive"))
      (node (ref "R57") (pin "2") (pinfunction "0_2") (pintype "passive"))
      (node (ref "U2") (pin "28") (pinfunction "PB2-BOOT1(PB2)_28") (pintype "bidirectional"))
    )
    (net (code "21") (name "/GPIO_7") (class "Default")
      (node (ref "J20") (pin "1") (pinfunction "A_1") (pintype "passive"))
      (node (ref "J3") (pin "17") (pinfunction "17_17") (pintype "passive"))
      (node (ref "R55") (pin "1") (pinfunction "0_1") (pintype "passive"))
    )
    (net (code "22") (name "/GPIO_7_FLT") (class "Default")
      (node (ref "J20") (pin "2") (pinfunction "B_2") (pintype "passive"))
      (node (ref "J24") (pin "1") (pinfunction "A_1") (pintype "passive"))
      (node (ref "R55") (pin "2") (pinfunction "0_2") (pintype "passive"))
      (node (ref "U2") (pin "50") (pinfunction "PA15(JTDI)_50") (pintype "bidirectional"))
    )
    (net (code "23") (name "/GPIO_8") (class "Default")
      (node (ref "J25") (pin "1") (pinfunction "A_1") (pintype "passive"))
      (node (ref "J3") (pin "18") (pinfunction "18_18") (pintype "passive"))
      (node (ref "R56") (pin "1") (pinfunction "0_1") (pintype "passive"))
    )
    (net (code "24") (name "/GPIO_8_FLT") (class "Default")
      (node (ref "J25") (pin "2") (pinfunction "B_2") (pintype "passive"))
      (node (ref "J26") (pin "1") (pinfunction "A_1") (pintype "passive"))
      (node (ref "R56") (pin "2") (pinfunction "0_2") (pintype "passive"))
      (node (ref "U2") (pin "55") (pinfunction "PB3(JTDO/TRACESWO)_55") (pintype "bidirectional"))
    )
    (net (code "25") (name "/M0_AH") (class "Default")
      (node (ref "U2") (pin "41") (pinfunction "PA8_41") (pintype "bidirectional"))
    )
    (net (code "26") (name "/M0_AL") (class "Default")
      (node (ref "U2") (pin "34") (pinfunction "PB13_34") (pintype "bidirectional"))
    )
    (net (code "27") (name "/M0_BH") (class "Default")
      (node (ref "U2") (pin "42") (pinfunction "PA9_42") (pintype "bidirectional"))
    )
    (net (code "28") (name "/M0_BL") (class "Default")
      (node (ref "U2") (pin "35") (pinfunction "PB14_35") (pintype "bidirectional"))
    )
    (net (code "29") (name "/M0_CH") (class "Default")
      (node (ref "U2") (pin "43") (pinfunction "PA10_43") (pintype "bidirectional"))
    )
    (net (code "30") (name "/M0_CL") (class "Default")
      (node (ref "U2") (pin "36") (pinfunction "PB15_36") (pintype "bidirectional"))
    )
    (net (code "31") (name "/M0_ENC_A") (class "Default")
      (node (ref "C73") (pin "1") (pinfunction "1_1") (pintype "passive"))
      (node (ref "J4") (pin "9") (pinfunction "9_9") (pintype "passive"))
      (node (ref "R9") (pin "1") (pinfunction "0_1") (pintype "passive"))
      (node (ref "U2") (pin "56") (pinfunction "PB4(NJTRST)_56") (pintype "bidirectional"))
    )
    (net (code "32") (name "/M0_ENC_B") (class "Default")
      (node (ref "C74") (pin "1") (pinfunction "1_1") (pintype "passive"))
      (node (ref "J4") (pin "10") (pinfunction "10_10") (pintype "passive"))
      (node (ref "R10") (pin "1") (pinfunction "0_1") (pintype "passive"))
      (node (ref "U2") (pin "57") (pinfunction "PB5_57") (pintype "bidirectional"))
    )
    (net (code "33") (name "/M0_ENC_Z") (class "Default")
      (node (ref "C75") (pin "1") (pinfunction "1_1") (pintype "passive"))
      (node (ref "J4") (pin "11") (pinfunction "11_11") (pintype "passive"))
      (node (ref "R11") (pin "1") (pinfunction "0_1") (pintype "passive"))
      (node (ref "U2") (pin "40") (pinfunction "PC9_40") (pintype "bidirectional"))
    )
    (net (code "34") (name "/M0_SO1") (class "Default")
      (node (ref "U2") (pin "8") (pinfunction "PC0_8") (pintype "bidirectional"))
    )
    (net (code "35") (name "/M0_SO2") (class "Default")
      (node (ref "U2") (pin "9") (pinfunction "PC1_9") (pintype "bidirectional"))
    )
    (net (code "36") (name "/M0_TEMP") (class "Default")
      (node (ref "U2") (pin "25") (pinfunction "PC5_25") (pintype "bidirectional"))
    )
    (net (code "37") (name "/M0_nCS") (class "Default")
      (node (ref "U2") (pin "2") (pinfunction "PC13_2") (pintype "bidirectional"))
    )
    (net (code "38") (name "/M1_AH") (class "Default")
      (node (ref "U2") (pin "37") (pinfunction "PC6_37") (pintype "bidirectional"))
    )
    (net (code "39") (name "/M1_AL") (class "Default")
      (node (ref "U2") (pin "23") (pinfunction "PA7_23") (pintype "bidirectional"))
    )
    (net (code "40") (name "/M1_BH") (class "Default")
      (node (ref "U2") (pin "38") (pinfunction "PC7_38") (pintype "bidirectional"))
    )
    (net (code "41") (name "/M1_BL") (class "Default")
      (node (ref "U2") (pin "26") (pinfunction "PB0_26") (pintype "bidirectional"))
    )
    (net (code "42") (name "/M1_CH") (class "Default")
      (node (ref "U2") (pin "39") (pinfunction "PC8_39") (pintype "bidirectional"))
    )
    (net (code "43") (name "/M1_CL") (class "Default")
      (node (ref "U2") (pin "27") (pinfunction "PB1_27") (pintype "bidirectional"))
    )
    (net (code "44") (name "/M1_ENC_A") (class "Default")
      (node (ref "C70") (pin "1") (pinfunction "1_1") (pintype "passive"))
      (node (ref "J4") (pin "3") (pinfunction "3_3") (pintype "passive"))
      (node (ref "R32") (pin "2") (pinfunction "0_2") (pintype "passive"))
      (node (ref "U2") (pin "58") (pinfunction "PB6_58") (pintype "bidirectional"))
    )
    (net (code "45") (name "/M1_ENC_B") (class "Default")
      (node (ref "C71") (pin "1") (pinfunction "1_1") (pintype "passive"))
      (node (ref "J4") (pin "4") (pinfunction "4_4") (pintype "passive"))
      (node (ref "R33") (pin "2") (pinfunction "0_2") (pintype "passive"))
      (node (ref "U2") (pin "59") (pinfunction "PB7_59") (pintype "bidirectional"))
    )
    (net (code "46") (name "/M1_ENC_Z") (class "Default")
      (node (ref "C72") (pin "1") (pinfunction "1_1") (pintype "passive"))
      (node (ref "J4") (pin "5") (pinfunction "5_5") (pintype "passive"))
      (node (ref "R34") (pin "2") (pinfunction "0_2") (pintype "passive"))
      (node (ref "U2") (pin "4") (pinfunction "PC15-OSC32_OUT(PC15)_4") (pintype "bidirectional"))
    )
    (net (code "47") (name "/M1_NCS") (class "Default")
      (node (ref "U2") (pin "3") (pinfunction "PC14-OSC32_IN(PC14)_3") (pintype "bidirectional"))
    )
    (net (code "48") (name "/M1_SO1") (class "Default")
      (node (ref "U2") (pin "11") (pinfunction "PC3_11") (pintype "bidirectional"))
    )
    (net (code "49") (name "/M1_SO2") (class "Default")
      (node (ref "U2") (pin "10") (pinfunction "PC2_10") (pintype "bidirectional"))
    )
    (net (code "50") (name "/M1_TEMP") (class "Default")
      (node (ref "U2") (pin "20") (pinfunction "PA4_20") (pintype "bidirectional"))
    )
    (net (code "52") (name "/SPI_MISO") (class "Default")
      (node (ref "J3") (pin "9") (pinfunction "9_9") (pintype "passive"))
      (node (ref "U2") (pin "52") (pinfunction "PC11_52") (pintype "bidirectional"))
    )
    (net (code "53") (name "/SPI_MOSI") (class "Default")
      (node (ref "J3") (pin "10") (pinfunction "10_10") (pintype "passive"))
      (node (ref "U2") (pin "53") (pinfunction "PC12_53") (pintype "bidirectional"))
    )
    (net (code "54") (name "/SPI_SCK") (class "Default")
      (node (ref "J3") (pin "8") (pinfunction "8_8") (pintype "passive"))
      (node (ref "U2") (pin "51") (pinfunction "PC10_51") (pintype "bidirectional"))
    )
    (net (code "55") (name "/SWCLK") (class "Default")
      (node (ref "R2") (pin "2") (pinfunction "0_2") (pintype "passive"))
      (node (ref "U2") (pin "49") (pinfunction "PA14(JTCK-SWCLK)_49") (pintype "bidirectional"))
    )
    (net (code "56") (name "/SWDIO") (class "Default")
      (node (ref "R4") (pin "2") (pinfunction "0_2") (pintype "passive"))
      (node (ref "U2") (pin "46") (pinfunction "PA13(JTMS-SWDIO)_46") (pintype "bidirectional"))
    )
    (net (code "57") (name "/USB_DM") (class "Default")
      (node (ref "R1") (pin "1") (pinfunction "0_1") (pintype "passive"))
      (node (ref "U2") (pin "44") (pinfunction "PA11_44") (pintype "bidirectional"))
    )
    (net (code "58") (name "/USB_DP") (class "Default")
      (node (ref "R3") (pin "1") (pinfunction "0_1") (pintype "passive"))
      (node (ref "U2") (pin "45") (pinfunction "PA12_45") (pintype "bidirectional"))
    )
    (net (code "59") (name "/VBUS_S") (class "Default")
      (node (ref "C1") (pin "2") (pinfunction "2_2") (pintype "passive"))
      (node (ref "R6") (pin "1") (pinfunction "0_1") (pintype "passive"))
      (node (ref "R7") (pin "2") (pinfunction "0_2") (pintype "passive"))
      (node (ref "U2") (pin "22") (pinfunction "PA6_22") (pintype "bidirectional"))
    )
    (net (code "60") (name "/nFAULT") (class "Default")
      (node (ref "U2") (pin "54") (pinfunction "PD2_54") (pintype "bidirectional"))
    )
    (net (code "63") (name "/nRST") (class "Default")
      (node (ref "C6") (pin "2") (pinfunction "2_2") (pintype "passive"))
      (node (ref "J2") (pin "6") (pinfunction "6_6") (pintype "passive"))
      (node (ref "U2") (pin "7") (pinfunction "NRST_7") (pintype "bidirectional"))
    )
    (net (code "64") (name "5V") (class "Default")
      (node (ref "C65") (pin "2") (pinfunction "2_2") (pintype "passive"))
      (node (ref "J2") (pin "1") (pinfunction "1_1") (pintype "passive"))
      (node (ref "J4") (pin "2") (pinfunction "2_2") (pintype "passive"))
      (node (ref "J4") (pin "8") (pinfunction "8_8") (pintype "passive"))
      (node (ref "U3") (pin "3") (pinfunction "Vin_3") (pintype "passive"))
      (node (ref "U8") (pin "1") (pinfunction "Vin_1") (pintype "passive"))
      (node (ref "U8") (pin "3") (pinfunction "ON/~{OFF}_3") (pintype "passive"))
    )
    (net (code "65") (name "AGND") (class "Default")
      (node (ref "C1") (pin "1") (pinfunction "1_1") (pintype "passive"))
      (node (ref "C21") (pin "1") (pinfunction "1_1") (pintype "passive"))
      (node (ref "C22") (pin "2") (pinfunction "2_2") (pintype "passive"))
      (node (ref "J3") (pin "7") (pinfunction "7_7") (pintype "passive"))
      (node (ref "NT1") (pin "2") (pintype "passive"))
      (node (ref "R7") (pin "1") (pinfunction "0_1") (pintype "passive"))
      (node (ref "TP5") (pin "1") (pintype "passive"))
      (node (ref "U2") (pin "12") (pinfunction "VSSA_12") (pintype "power_in"))
      (node (ref "U8") (pin "2") (pinfunction "GND_2") (pintype "passive"))
    )
    (net (code "66") (name "AVCC") (class "Default")
      (node (ref "C21") (pin "2") (pinfunction "2_2") (pintype "passive"))
      (node (ref "C22") (pin "1") (pinfunction "1_1") (pintype "passive"))
      (node (ref "J3") (pin "6") (pinfunction "6_6") (pintype "passive"))
      (node (ref "TP4") (pin "1") (pintype "passive"))
      (node (ref "U2") (pin "13") (pinfunction "VDDA_13") (pintype "power_in"))
      (node (ref "U8") (pin "4") (pinfunction "N/C_4") (pintype "passive"))
      (node (ref "U8") (pin "5") (pinfunction "Vout_5") (pintype "passive"))
    )
    (net (code "67") (name "DCBUS") (class "Default")
      (node (ref "C11") (pin "1") (pinfunction "1_1") (pintype "passive"))
      (node (ref "C12") (pin "1") (pinfunction "1_1") (pintype "passive"))
      (node (ref "C13") (pin "1") (pinfunction "1_1") (pintype "passive"))
      (node (ref "C14") (pin "1") (pinfunction "1_1") (pintype "passive"))
      (node (ref "C15") (pin "1") (pinfunction "1_1") (pintype "passive"))
      (node (ref "C16") (pin "1") (pinfunction "1_1") (pintype "passive"))
      (node (ref "C17") (pin "1") (pinfunction "1_1") (pintype "passive"))
      (node (ref "C18") (pin "1") (pinfunction "1_1") (pintype "passive"))
      (node (ref "C26") (pin "2") (pinfunction "2_2") (pintype "passive"))
      (node (ref "C40") (pin "2") (pinfunction "2_2") (pintype "passive"))
      (node (ref "C44") (pin "2") (pinfunction "2_2") (pintype "passive"))
      (node (ref "C55") (pin "2") (pinfunction "2_2") (pintype "passive"))
      (node (ref "C68") (pin "2") (pinfunction "2_2") (pintype "passive"))
      (node (ref "J7") (pin "1") (pinfunction "1_1") (pintype "passive"))
      (node (ref "J9") (pin "2") (pinfunction "2_2") (pintype "passive"))
      (node (ref "R6") (pin "2") (pinfunction "0_2") (pintype "passive"))
    )
    (net (code "68") (name "GND") (class "Default")
      (node (ref "C10") (pin "2") (pinfunction "2_2") (pintype "passive"))
      (node (ref "C19") (pin "1") (pinfunction "1_1") (pintype "passive"))
      (node (ref "C2") (pin "2") (pinfunction "2_2") (pintype "passive"))
      (node (ref "C20") (pin "1") (pinfunction "1_1") (pintype "passive"))
      (node (ref "C3") (pin "2") (pinfunction "2_2") (pintype "passive"))
      (node (ref "C4") (pin "1") (pinfunction "1_1") (pintype "passive"))
      (node (ref "C5") (pin "1") (pinfunction "1_1") (pintype "passive"))
      (node (ref "C6") (pin "1") (pinfunction "1_1") (pintype "passive"))
      (node (ref "C62") (pin "1") (pinfunction "1_1") (pintype "passive"))
      (node (ref "C63") (pin "2") (pinfunction "2_2") (pintype "passive"))
      (node (ref "C64") (pin "2") (pinfunction "2_2") (pintype "passive"))
      (node (ref "C65") (pin "1") (pinfunction "1_1") (pintype "passive"))
      (node (ref "C66") (pin "2") (pinfunction "2_2") (pintype "passive"))
      (node (ref "C67") (pin "2") (pinfunction "2_2") (pintype "passive"))
      (node (ref "C69") (pin "2") (pinfunction "2_2") (pintype "passive"))
      (node (ref "C7") (pin "2") (pinfunction "2_2") (pintype "passive"))
      (node (ref "C70") (pin "2") (pinfunction "2_2") (pintype "passive"))
      (node (ref "C71") (pin "2") (pinfunction "2_2") (pintype "passive"))
      (node (ref "C72") (pin "2") (pinfunction "2_2") (pintype "passive"))
      (node (ref "C73") (pin "2") (pinfunction "2_2") (pintype "passive"))
      (node (ref "C74") (pin "2") (pinfunction "2_2") (pintype "passive"))
      (node (ref "C75") (pin "2") (pinfunction "2_2") (pintype "passive"))
      (node (ref "C8") (pin "2") (pinfunction "2_2") (pintype "passive"))
      (node (ref "C9") (pin "2") (pinfunction "2_2") (pintype "passive"))
      (node (ref "J1") (pin "5") (pinfunction "GND_5") (pintype "passive"))
      (node (ref "J1") (pin "SH") (pinfunction "SHIELD_SH") (pintype "passive"))
      (node (ref "J2") (pin "4") (pinfunction "4_4") (pintype "passive"))
      (node (ref "J3") (pin "19") (pinfunction "19_19") (pintype "passive"))
      (node (ref "J3") (pin "2") (pinfunction "2_2") (pintype "passive"))
      (node (ref "J3") (pin "20") (pinfunction "20_20") (pintype "passive"))
      (node (ref "J3") (pin "5") (pinfunction "5_5") (pintype "passive"))
      (node (ref "J4") (pin "12") (pinfunction "12_12") (pintype "passive"))
      (node (ref "J4") (pin "6") (pinfunction "6_6") (pintype "passive"))
      (node (ref "NT1") (pin "1") (pintype "passive"))
      (node (ref "R58") (pin "2") (pinfunction "0_2") (pintype "passive"))
      (node (ref "R59") (pin "2") (pinfunction "0_2") (pintype "passive"))
      (node (ref "R60") (pin "2") (pinfunction "0_2") (pintype "passive"))
      (node (ref "SW1") (pin "2") (pinfunction "A2_2") (pintype "passive"))
      (node (ref "TP3") (pin "1") (pintype "passive"))
      (node (ref "U1") (pin "2") (pinfunction "GND_2") (pintype "passive"))
      (node (ref "U2") (pin "18") (pinfunction "VSS_18") (pintype "power_in"))
      (node (ref "U2") (pin "63") (pinfunction "VSS_63") (pintype "power_in"))
      (node (ref "U3") (pin "1") (pinfunction "GND_1") (pintype "passive"))
      (node (ref "XT1") (pin "G") (pintype "passive"))
    )
    (net (code "69") (name "Net-(C63-Pad1)") (class "Default")
      (node (ref "C63") (pin "1") (pinfunction "1_1") (pintype "passive"))
      (node (ref "J6") (pin "2") (pinfunction "A_2") (pintype "passive"))
    )
    (net (code "70") (name "Net-(C64-Pad1)") (class "Default")
      (node (ref "C64") (pin "1") (pinfunction "1_1") (pintype "passive"))
      (node (ref "J15") (pin "2") (pinfunction "A_2") (pintype "passive"))
    )
    (net (code "71") (name "Net-(C66-Pad1)") (class "Default")
      (node (ref "C66") (pin "1") (pinfunction "1_1") (pintype "passive"))
      (node (ref "J24") (pin "2") (pinfunction "A_2") (pintype "passive"))
    )
    (net (code "72") (name "Net-(C67-Pad1)") (class "Default")
      (node (ref "C67") (pin "1") (pinfunction "1_1") (pintype "passive"))
      (node (ref "J26") (pin "2") (pinfunction "A_2") (pintype "passive"))
    )
    (net (code "73") (name "Net-(C69-Pad1)") (class "Default")
      (node (ref "C69") (pin "1") (pinfunction "1_1") (pintype "passive"))
      (node (ref "J28") (pin "2") (pinfunction "A_2") (pintype "passive"))
    )
    (net (code "74") (name "Net-(J1-D+)") (class "Default")
      (node (ref "J1") (pin "3") (pinfunction "D+_3") (pintype "passive"))
      (node (ref "R3") (pin "2") (pinfunction "0_2") (pintype "passive"))
      (node (ref "TP2") (pin "1") (pintype "passive"))
    )
    (net (code "75") (name "Net-(J1-D-)") (class "Default")
      (node (ref "J1") (pin "2") (pinfunction "D-_2") (pintype "passive"))
      (node (ref "R1") (pin "2") (pinfunction "0_2") (pintype "passive"))
      (node (ref "TP1") (pin "1") (pintype "passive"))
    )
    (net (code "76") (name "Net-(J2-Pad3)") (class "Default")
      (node (ref "J2") (pin "3") (pinfunction "3_3") (pintype "passive"))
      (node (ref "R2") (pin "1") (pinfunction "0_1") (pintype "passive"))
    )
    (net (code "77") (name "Net-(J2-Pad5)") (class "Default")
      (node (ref "J2") (pin "5") (pinfunction "5_5") (pintype "passive"))
      (node (ref "R4") (pin "1") (pinfunction "0_1") (pintype "passive"))
    )
    (net (code "78") (name "Net-(LED1-PadK)") (class "Default")
      (node (ref "LED1") (pin "K") (pinfunction "K_K") (pintype "passive"))
      (node (ref "R58") (pin "1") (pinfunction "0_1") (pintype "passive"))
    )
    (net (code "79") (name "Net-(SW1-B1)") (class "Default")
      (node (ref "R5") (pin "1") (pinfunction "0_1") (pintype "passive"))
      (node (ref "SW1") (pin "4") (pinfunction "B1_4") (pintype "passive"))
    )
    (net (code "80") (name "Net-(U2A-PH0-OSC_IN(PH0))") (class "Default")
      (node (ref "C3") (pin "1") (pinfunction "1_1") (pintype "passive"))
      (node (ref "U2") (pin "5") (pinfunction "PH0-OSC_IN(PH0)_5") (pintype "bidirectional"))
      (node (ref "XT1") (pin "3") (pintype "passive"))
    )
    (net (code "81") (name "Net-(U2A-PH1-OSC_OUT(PH1))") (class "Default")
      (node (ref "C2") (pin "1") (pinfunction "1_1") (pintype "passive"))
      (node (ref "U2") (pin "6") (pinfunction "PH1-OSC_OUT(PH1)_6") (pintype "bidirectional"))
      (node (ref "XT1") (pin "1") (pintype "passive"))
    )
    (net (code "82") (name "Net-(U2A-VCAP_1)") (class "Default")
      (node (ref "C5") (pin "2") (pinfunction "2_2") (pintype "passive"))
      (node (ref "U2") (pin "31") (pinfunction "VCAP_1_31") (pintype "power_in"))
    )
    (net (code "83") (name "Net-(U2A-VCAP_2)") (class "Default")
      (node (ref "C4") (pin "2") (pinfunction "2_2") (pintype "passive"))
      (node (ref "U2") (pin "47") (pinfunction "VCAP_2_47") (pintype "power_in"))
    )
    (net (code "84") (name "PGND") (class "Default")
      (node (ref "C11") (pin "2") (pinfunction "2_2") (pintype "passive"))
      (node (ref "C12") (pin "2") (pinfunction "2_2") (pintype "passive"))
      (node (ref "C13") (pin "2") (pinfunction "2_2") (pintype "passive"))
      (node (ref "C14") (pin "2") (pinfunction "2_2") (pintype "passive"))
      (node (ref "C15") (pin "2") (pinfunction "2_2") (pintype "passive"))
      (node (ref "C16") (pin "2") (pinfunction "2_2") (pintype "passive"))
      (node (ref "C17") (pin "2") (pinfunction "2_2") (pintype "passive"))
      (node (ref "C18") (pin "2") (pinfunction "2_2") (pintype "passive"))
      (node (ref "C26") (pin "1") (pinfunction "1_1") (pintype "passive"))
      (node (ref "C40") (pin "1") (pinfunction "1_1") (pintype "passive"))
      (node (ref "C44") (pin "1") (pinfunction "1_1") (pintype "passive"))
      (node (ref "C55") (pin "1") (pinfunction "1_1") (pintype "passive"))
      (node (ref "C68") (pin "1") (pinfunction "1_1") (pintype "passive"))
      (node (ref "J8") (pin "1") (pinfunction "1_1") (pintype "passive"))
      (node (ref "J9") (pin "1") (pinfunction "1_1") (pintype "passive"))
    )
    (net (code "85") (name "VCC") (class "Default")
      (node (ref "C10") (pin "1") (pinfunction "1_1") (pintype "passive"))
      (node (ref "C19") (pin "2") (pinfunction "2_2") (pintype "passive"))
      (node (ref "C20") (pin "2") (pinfunction "2_2") (pintype "passive"))
      (node (ref "C62") (pin "2") (pinfunction "2_2") (pintype "passive"))
      (node (ref "C7") (pin "1") (pinfunction "1_1") (pintype "passive"))
      (node (ref "C8") (pin "1") (pinfunction "1_1") (pintype "passive"))
      (node (ref "C9") (pin "1") (pinfunction "1_1") (pintype "passive"))
      (node (ref "J2") (pin "2") (pinfunction "2_2") (pintype "passive"))
      (node (ref "J3") (pin "1") (pinfunction "1_1") (pintype "passive"))
      (node (ref "J4") (pin "1") (pinfunction "1_1") (pintype "passive"))
      (node (ref "J4") (pin "7") (pinfunction "7_7") (pintype "passive"))
      (node (ref "LED1") (pin "A") (pinfunction "A_A") (pintype "passive"))
      (node (ref "R10") (pin "2") (pinfunction "0_2") (pintype "passive"))
      (node (ref "R11") (pin "2") (pinfunction "0_2") (pintype "passive"))
      (node (ref "R32") (pin "1") (pinfunction "0_1") (pintype "passive"))
      (node (ref "R33") (pin "1") (pinfunction "0_1") (pintype "passive"))
      (node (ref "R34") (pin "1") (pinfunction "0_1") (pintype "passive"))
      (node (ref "R8") (pin "1") (pinfunction "0_1") (pintype "passive"))
      (node (ref "R9") (pin "2") (pinfunction "0_2") (pintype "passive"))
      (node (ref "U1") (pin "3") (pinfunction "VCC_3") (pintype "passive"))
      (node (ref "U2") (pin "1") (pinfunction "VBAT_1") (pintype "power_in"))
      (node (ref "U2") (pin "19") (pinfunction "VDD_19") (pintype "power_in"))
      (node (ref "U2") (pin "32") (pinfunction "VDD_32") (pintype "power_in"))
      (node (ref "U2") (pin "48") (pinfunction "VDD_48") (pintype "power_in"))
      (node (ref "U2") (pin "64") (pinfunction "VDD_64") (pintype "power_in"))
      (node (ref "U3") (pin "2") (pinfunction "Vout_2") (pintype "passive"))
      (node (ref "U3") (pin "4") (pinfunction "Vout_(tab)_4") (pintype "passive"))
    )
    (net (code "86") (name "unconnected-(J1-ID-Pad4)") (class "Default")
      (node (ref "J1") (pin "4") (pinfunction "ID_4") (pintype "passive"))
    )
    (net (code "87") (name "unconnected-(J1-VCC-Pad1)") (class "Default")
      (node (ref "J1") (pin "1") (pinfunction "VCC_1") (pintype "passive"))
    )
    (net (code "88") (name "unconnected-(U1-NC-Pad5)") (class "Default")
      (node (ref "U1") (pin "5") (pinfunction "NC_5") (pintype "passive"))
    )
    (net (code "89") (name "unconnected-(U1-NC-Pad8)") (class "Default")
      (node (ref "U1") (pin "8") (pinfunction "NC_8") (pintype "passive"))
    )
  )
)
